# SCH_fluffly_2_2024-03-27.net
KiCad netlist of a schematic drawn in EasyEDA
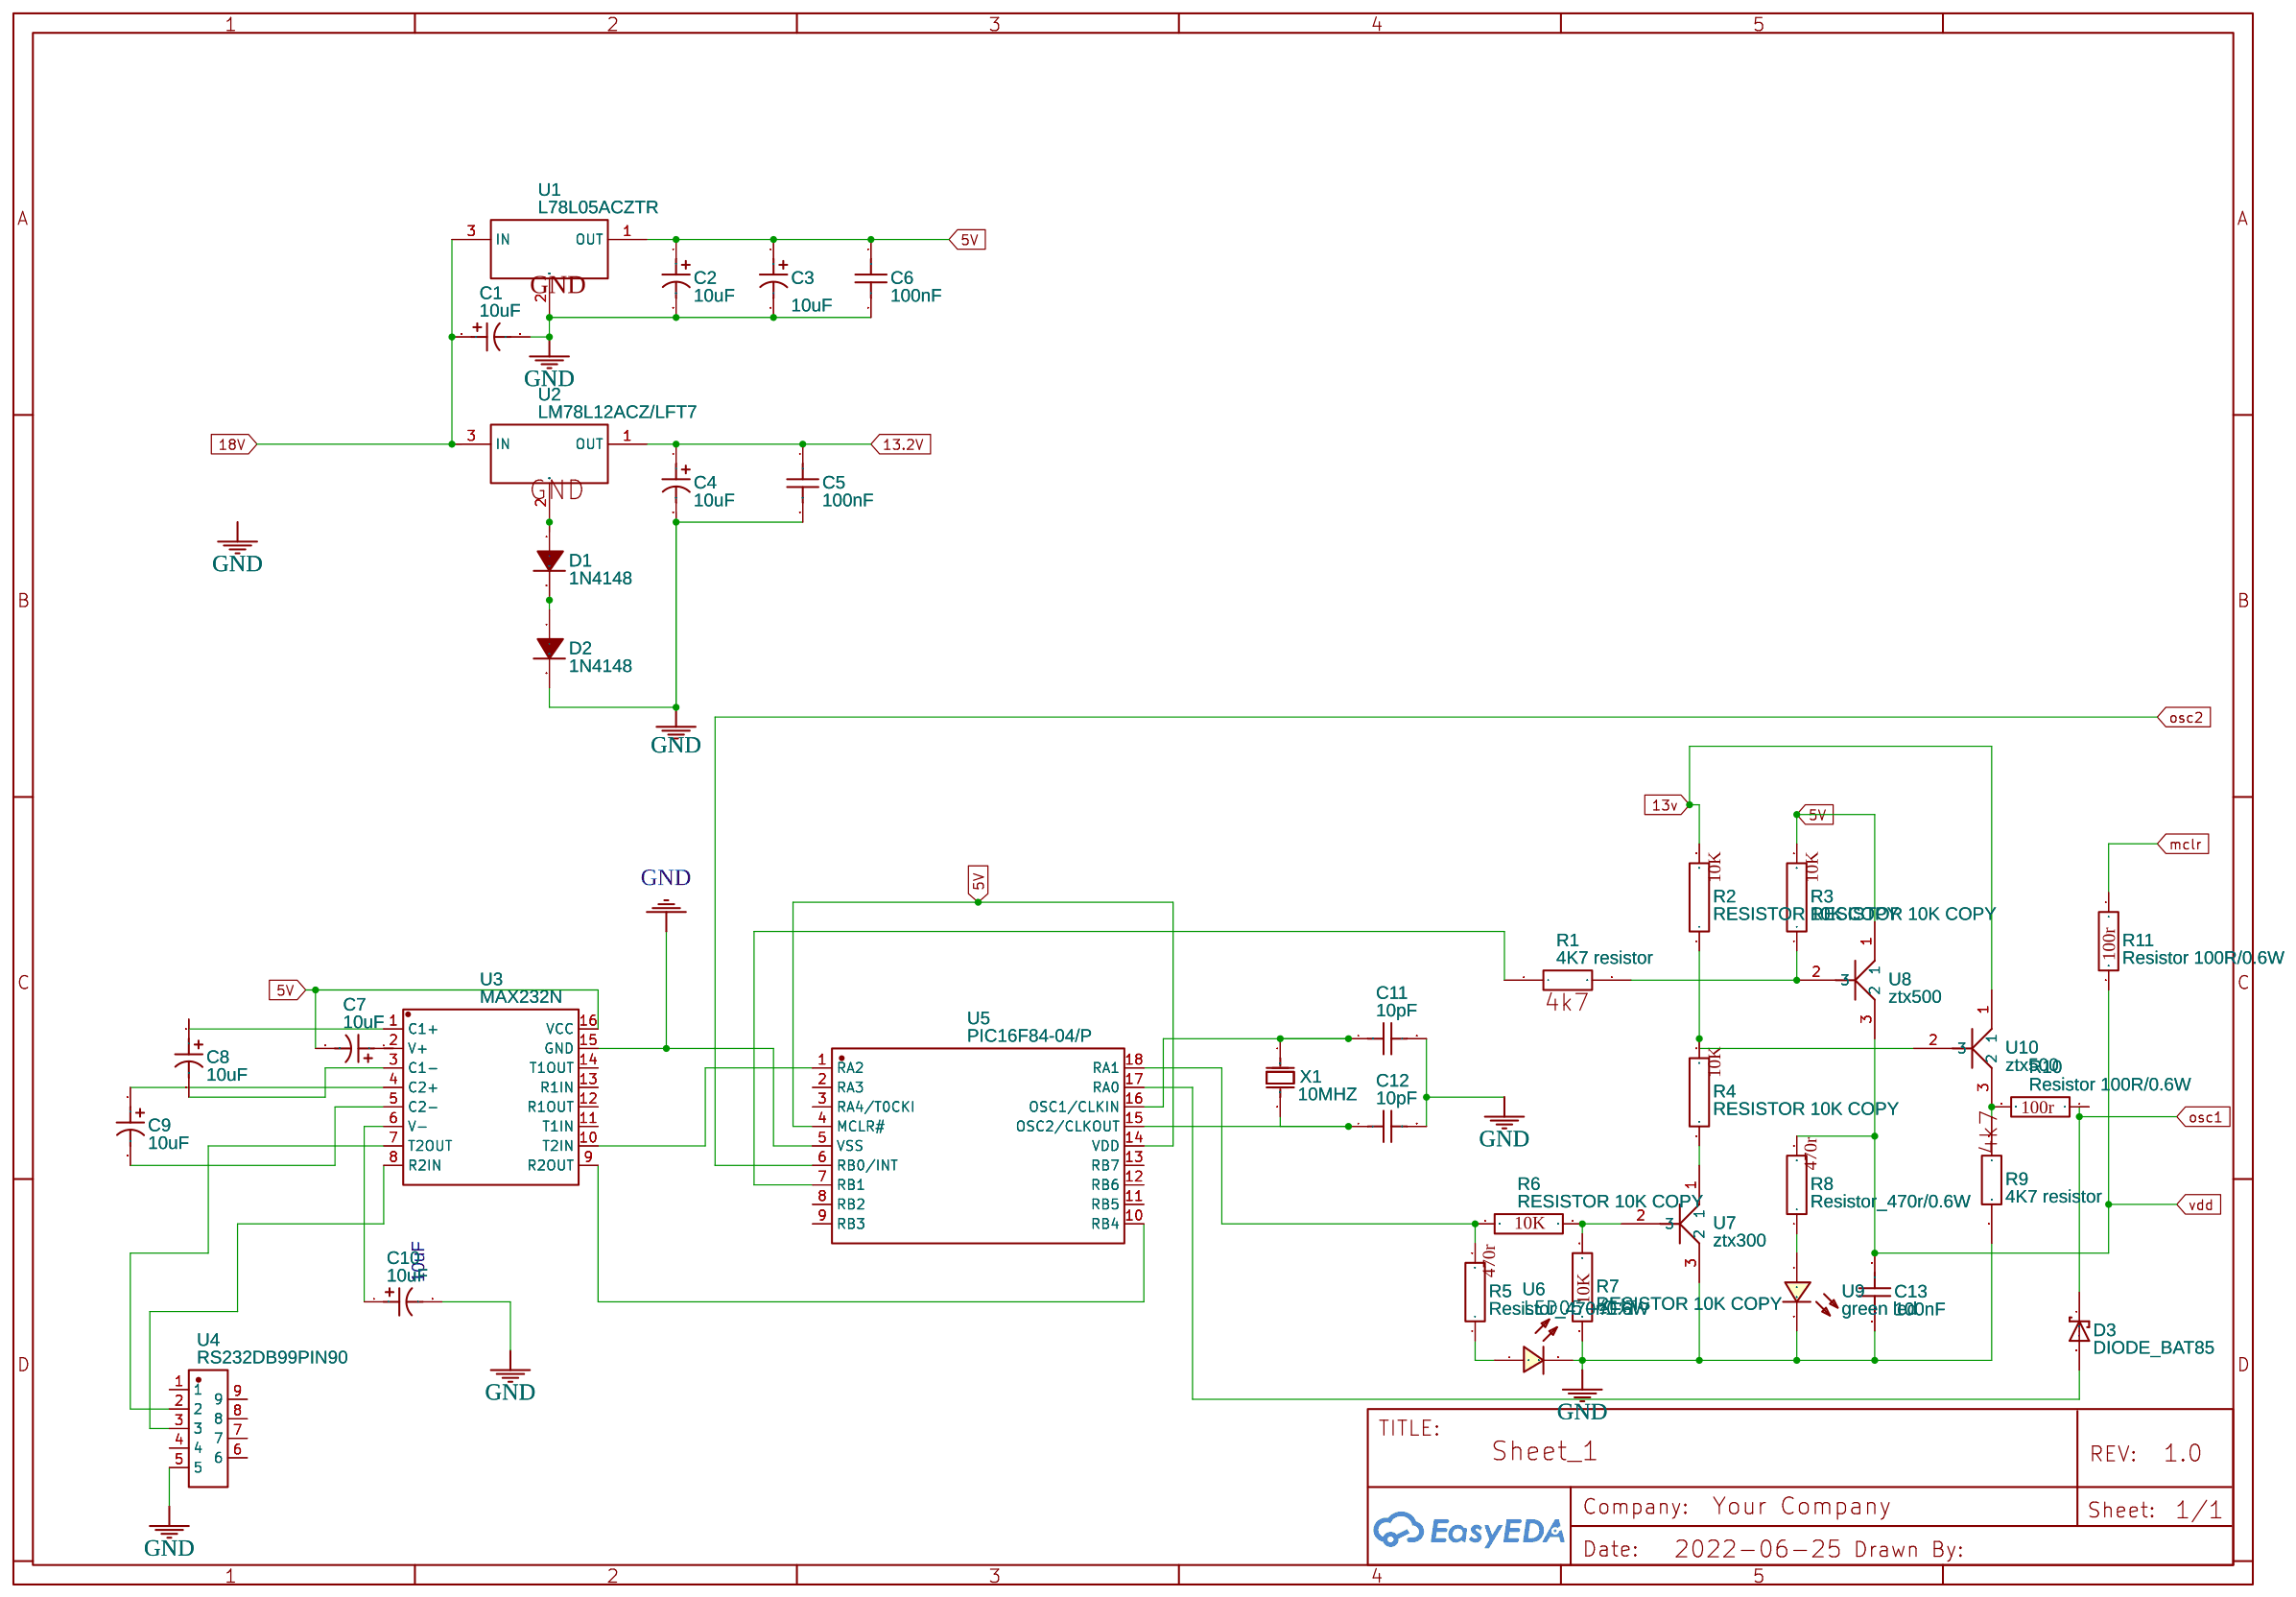
[diagram p0: schematic sheet]

(export (version "E")
  (design (tool "Eeschema 10.0.6"))
  (components
    (comp (ref "C1")
      (value "10uF")
      (fields (field (name "Manufacturer Part") "RFS-50V100MG3#") (field (name "Manufacturer") "ELNA(伊娜)"))
      (libsource (lib "") (part "RFS-50V100MG3#_3"))
    )
    (comp (ref "C2")
      (value "10uF")
      (fields (field (name "Manufacturer Part") "RFS-50V100MG3#") (field (name "Manufacturer") "ELNA(伊娜)"))
      (libsource (lib "") (part "RFS-50V100MG3#_1"))
    )
    (comp (ref "C3")
      (value "10uF")
      (fields (field (name "Manufacturer Part") "RFS-50V100MG3#") (field (name "Manufacturer") "ELNA(伊娜)"))
      (libsource (lib "") (part "RFS-50V100MG3#_1"))
    )
    (comp (ref "C4")
      (value "10uF")
      (fields (field (name "Manufacturer Part") "RFS-50V100MG3#") (field (name "Manufacturer") "ELNA(伊娜)"))
      (libsource (lib "") (part "RFS-50V100MG3#_1"))
    )
    (comp (ref "C5")
      (value "100nF")
      (fields
        (field (name "Manufacturer Part") "DCS104Z26Y5VF58L5A0")
        (field (name "Manufacturer") "SHM(南方宏明)")
      )
      (libsource (lib "") (part "DCS104Z26Y5VF58L5A0"))
    )
    (comp (ref "C6")
      (value "100nF")
      (fields
        (field (name "Manufacturer Part") "DCS104Z26Y5VF58L5A0")
        (field (name "Manufacturer") "SHM(南方宏明)")
      )
      (libsource (lib "") (part "DCS104Z26Y5VF58L5A0"))
    )
    (comp (ref "C7")
      (value "10uF")
      (fields (field (name "Manufacturer Part") "RFS-50V100MG3#") (field (name "Manufacturer") "ELNA(伊娜)"))
      (libsource (lib "") (part "RFS-50V100MG3#_2"))
    )
    (comp (ref "C8")
      (value "10uF")
      (fields (field (name "Manufacturer Part") "RFS-50V100MG3#") (field (name "Manufacturer") "ELNA(伊娜)"))
      (libsource (lib "") (part "RFS-50V100MG3#"))
    )
    (comp (ref "C9")
      (value "10uF")
      (fields (field (name "Manufacturer Part") "RFS-50V100MG3#") (field (name "Manufacturer") "ELNA(伊娜)"))
      (libsource (lib "") (part "RFS-50V100MG3#_1"))
    )
    (comp (ref "C10")
      (value "10uF")
      (fields (field (name "Manufacturer Part") "RFS-50V100MG3#") (field (name "Manufacturer") "ELNA(伊娜)"))
      (libsource (lib "") (part "RFS-50V100MG3#_4"))
    )
    (comp (ref "C11")
      (value "10pF")
      (fields (field (name "Manufacturer Part") "CC45SL3FD100JYNNA") (field (name "Manufacturer") "TDK"))
      (libsource (lib "") (part "CC45SL3FD100JYNNA"))
    )
    (comp (ref "C12")
      (value "10pF")
      (fields (field (name "Manufacturer Part") "CC45SL3FD100JYNNA") (field (name "Manufacturer") "TDK"))
      (libsource (lib "") (part "CC45SL3FD100JYNNA"))
    )
    (comp (ref "C13")
      (value "100nF")
      (fields
        (field (name "Manufacturer Part") "DCS104Z26Y5VF58L5A0")
        (field (name "Manufacturer") "SHM(南方宏明)")
      )
      (libsource (lib "") (part "DCS104Z26Y5VF58L5A0"))
    )
    (comp (ref "D1")
      (value "1N4148")
      (fields (field (name "Manufacturer") "SEMTECH"))
      (libsource (lib "") (part "1N4148"))
    )
    (comp (ref "D2")
      (value "1N4148")
      (fields (field (name "Manufacturer") "SEMTECH"))
      (libsource (lib "") (part "1N4148"))
    )
    (comp (ref "D3") (value "DIODE_BAT85") (libsource (lib "") (part "DIODE_BAT85")))
    (comp (ref "R1") (value "4K7 resistor") (libsource (lib "") (part "4K7 resistor")))
    (comp (ref "R2") (value "RESISTOR 10K COPY") (libsource (lib "") (part "RESISTOR 10K COPY")))
    (comp (ref "R3") (value "RESISTOR 10K COPY") (libsource (lib "") (part "RESISTOR 10K COPY")))
    (comp (ref "R4") (value "RESISTOR 10K COPY") (libsource (lib "") (part "RESISTOR 10K COPY")))
    (comp (ref "R5") (value "Resistor_470r/0.6W") (libsource (lib "") (part "Resistor_470r/0.6W")))
    (comp (ref "R6") (value "RESISTOR 10K COPY") (libsource (lib "") (part "RESISTOR 10K COPY_1")))
    (comp (ref "R7") (value "RESISTOR 10K COPY") (libsource (lib "") (part "RESISTOR 10K COPY_2")))
    (comp (ref "R8") (value "Resistor_470r/0.6W") (libsource (lib "") (part "Resistor_470r/0.6W")))
    (comp (ref "R9") (value "4K7 resistor") (libsource (lib "") (part "4K7 resistor_1")))
    (comp (ref "R10") (value "Resistor 100R/0.6W") (libsource (lib "") (part "Resistor 100R/0.6W_1")))
    (comp (ref "R11") (value "Resistor 100R/0.6W") (libsource (lib "") (part "Resistor 100R/0.6W")))
    (comp (ref "U1")
      (value "L78L05ACZTR")
      (fields (field (name "Manufacturer") "STMicroelectronics"))
      (libsource (lib "") (part "L78L05ACZTR"))
    )
    (comp (ref "U2")
      (value "LM78L12ACZ/LFT7")
      (fields (field (name "Manufacturer") "TI(德州仪器)"))
      (libsource (lib "") (part "LM78L12ACZ/LFT7"))
    )
    (comp (ref "U3")
      (value "MAX232N")
      (fields (field (name "Manufacturer") "Texas Instruments"))
      (libsource (lib "") (part "MAX232N"))
    )
    (comp (ref "U4")
      (value "RS232DB99PIN90")
      (fields (field (name "Manufacturer Part") "RS232DB99pin90度母座"))
      (libsource (lib "") (part "RS232DB99PIN90"))
    )
    (comp (ref "U5")
      (value "PIC16F84-04/P")
      (fields (field (name "Manufacturer") "Microchip Tech"))
      (libsource (lib "") (part "PIC16F84-04/P"))
    )
    (comp (ref "U6") (value "LED05-红灯") (libsource (lib "") (part "LED05-红灯")))
    (comp (ref "U7") (value "ztx300") (libsource (lib "") (part "transistor")))
    (comp (ref "U8") (value "ztx500") (libsource (lib "") (part "transistor")))
    (comp (ref "U9")
      (value "green led")
      (fields (field (name "Manufacturer Part") "LED05-红灯"))
      (libsource (lib "") (part "LED05-红灯_1"))
    )
    (comp (ref "U10") (value "ztx500") (libsource (lib "") (part "transistor")))
    (comp (ref "X1")
      (value "10MHZ")
      (fields (field (name "Manufacturer Part") "509-0400A2020-00") (field (name "Manufacturer") "XTY"))
      (libsource (lib "") (part "509-0400A2020-00"))
    )
  )
  (nets
    (net (code "1") (name "5V") (class "Default")
      (node (ref "C2") (pin "1") (pinfunction "1_1") (pintype "input"))
      (node (ref "C3") (pin "1") (pinfunction "1_1") (pintype "input"))
      (node (ref "C6") (pin "1") (pinfunction "1_1") (pintype "unspecified"))
      (node (ref "C7") (pin "2") (pinfunction "2_2") (pintype "input"))
      (node (ref "R3") (pin "2") (pinfunction "2_2") (pintype "unspecified"))
      (node (ref "U1") (pin "1") (pinfunction "OUT_1") (pintype "passive"))
      (node (ref "U3") (pin "16") (pinfunction "VCC_16") (pintype "unspecified"))
      (node (ref "U5") (pin "14") (pinfunction "VDD_14") (pintype "unspecified"))
      (node (ref "U5") (pin "4") (pinfunction "MCLR#_4") (pintype "unspecified"))
      (node (ref "U8") (pin "1") (pinfunction "1_1") (pintype "unspecified"))
    )
    (net (code "2") (name "13.2V") (class "Default")
      (node (ref "C4") (pin "1") (pinfunction "1_1") (pintype "input"))
      (node (ref "C5") (pin "1") (pinfunction "1_1") (pintype "unspecified"))
      (node (ref "U2") (pin "1") (pinfunction "OUT_1") (pintype "passive"))
    )
    (net (code "3") (name "13v") (class "Default")
      (node (ref "R2") (pin "2") (pinfunction "2_2") (pintype "unspecified"))
      (node (ref "U10") (pin "1") (pinfunction "1_1") (pintype "unspecified"))
    )
    (net (code "4") (name "18V") (class "Default")
      (node (ref "C1") (pin "1") (pinfunction "1_1") (pintype "input"))
      (node (ref "U1") (pin "3") (pinfunction "IN_3") (pintype "passive"))
      (node (ref "U2") (pin "3") (pinfunction "IN_3") (pintype "passive"))
    )
    (net (code "5") (name "GND") (class "Default")
      (node (ref "C1") (pin "2") (pinfunction "2_2") (pintype "input"))
      (node (ref "C10") (pin "2") (pinfunction "2_2") (pintype "input"))
      (node (ref "C11") (pin "2") (pinfunction "2_2") (pintype "unspecified"))
      (node (ref "C12") (pin "2") (pinfunction "2_2") (pintype "unspecified"))
      (node (ref "C13") (pin "2") (pinfunction "2_2") (pintype "unspecified"))
      (node (ref "C2") (pin "2") (pinfunction "2_2") (pintype "input"))
      (node (ref "C3") (pin "2") (pinfunction "2_2") (pintype "input"))
      (node (ref "C4") (pin "2") (pinfunction "2_2") (pintype "input"))
      (node (ref "C5") (pin "2") (pinfunction "2_2") (pintype "unspecified"))
      (node (ref "C6") (pin "2") (pinfunction "2_2") (pintype "unspecified"))
      (node (ref "D2") (pin "2") (pinfunction "C_2") (pintype "unspecified"))
      (node (ref "R7") (pin "1") (pinfunction "1_1") (pintype "unspecified"))
      (node (ref "R9") (pin "2") (pinfunction "2_2") (pintype "unspecified"))
      (node (ref "U1") (pin "2") (pinfunction "GND_2") (pintype "passive"))
      (node (ref "U3") (pin "15") (pinfunction "GND_15") (pintype "unspecified"))
      (node (ref "U4") (pin "5") (pinfunction "5_5") (pintype "unspecified"))
      (node (ref "U5") (pin "5") (pinfunction "VSS_5") (pintype "unspecified"))
      (node (ref "U6") (pin "2") (pinfunction "2_2") (pintype "unspecified"))
      (node (ref "U7") (pin "3") (pinfunction "2_3") (pintype "unspecified"))
      (node (ref "U9") (pin "2") (pinfunction "2_2") (pintype "unspecified"))
    )
    (net (code "6") (name "Net-(D1-A)") (class "Default")
      (node (ref "D1") (pin "1") (pinfunction "A_1") (pintype "unspecified"))
      (node (ref "U2") (pin "2") (pinfunction "GND_2") (pintype "passive"))
    )
    (net (code "7") (name "Net-(D1-C)") (class "Default")
      (node (ref "D1") (pin "2") (pinfunction "C_2") (pintype "unspecified"))
      (node (ref "D2") (pin "1") (pinfunction "A_1") (pintype "unspecified"))
    )
    (net (code "8") (name "Net-(D3-A)") (class "Default")
      (node (ref "D3") (pin "2") (pinfunction "A_2") (pintype "unspecified"))
      (node (ref "U5") (pin "17") (pinfunction "RA0_17") (pintype "unspecified"))
    )
    (net (code "9") (name "Net-(R4-Pad1)") (class "Default")
      (node (ref "R4") (pin "1") (pinfunction "1_1") (pintype "unspecified"))
      (node (ref "U7") (pin "1") (pinfunction "1_1") (pintype "unspecified"))
    )
    (net (code "10") (name "Net-(R5-Pad1)") (class "Default")
      (node (ref "R5") (pin "1") (pinfunction "1_1") (pintype "unspecified"))
      (node (ref "U6") (pin "1") (pinfunction "1_1") (pintype "unspecified"))
    )
    (net (code "11") (name "Net-(R8-Pad1)") (class "Default")
      (node (ref "R8") (pin "1") (pinfunction "1_1") (pintype "unspecified"))
      (node (ref "U9") (pin "1") (pinfunction "1_1") (pintype "unspecified"))
    )
    (net (code "12") (name "Net-(U3-C1+)") (class "Default")
      (node (ref "C8") (pin "1") (pinfunction "1_1") (pintype "input"))
      (node (ref "U3") (pin "1") (pinfunction "C1+_1") (pintype "unspecified"))
    )
    (net (code "13") (name "Net-(U3-C1-)") (class "Default")
      (node (ref "C8") (pin "2") (pinfunction "2_2") (pintype "input"))
      (node (ref "U3") (pin "3") (pinfunction "C1-_3") (pintype "unspecified"))
    )
    (net (code "14") (name "Net-(U3-C2+)") (class "Default")
      (node (ref "C9") (pin "1") (pinfunction "1_1") (pintype "input"))
      (node (ref "U3") (pin "4") (pinfunction "C2+_4") (pintype "unspecified"))
    )
    (net (code "15") (name "Net-(U3-C2-)") (class "Default")
      (node (ref "C9") (pin "2") (pinfunction "2_2") (pintype "input"))
      (node (ref "U3") (pin "5") (pinfunction "C2-_5") (pintype "unspecified"))
    )
    (net (code "16") (name "Net-(U3-R2IN)") (class "Default")
      (node (ref "U3") (pin "8") (pinfunction "R2IN_8") (pintype "unspecified"))
      (node (ref "U4") (pin "3") (pinfunction "3_3") (pintype "unspecified"))
    )
    (net (code "17") (name "Net-(U3-R2OUT)") (class "Default")
      (node (ref "U3") (pin "9") (pinfunction "R2OUT_9") (pintype "unspecified"))
      (node (ref "U5") (pin "10") (pinfunction "RB4_10") (pintype "unspecified"))
    )
    (net (code "18") (name "Net-(U3-T2IN)") (class "Default")
      (node (ref "U3") (pin "10") (pinfunction "T2IN_10") (pintype "unspecified"))
      (node (ref "U5") (pin "1") (pinfunction "RA2_1") (pintype "unspecified"))
    )
    (net (code "19") (name "Net-(U3-T2OUT)") (class "Default")
      (node (ref "U3") (pin "7") (pinfunction "T2OUT_7") (pintype "unspecified"))
      (node (ref "U4") (pin "2") (pinfunction "2_2") (pintype "unspecified"))
    )
    (net (code "20") (name "Net-(U3-V+)") (class "Default")
      (node (ref "C7") (pin "1") (pinfunction "1_1") (pintype "input"))
      (node (ref "U3") (pin "2") (pinfunction "V+_2") (pintype "unspecified"))
    )
    (net (code "21") (name "Net-(U3-V-)") (class "Default")
      (node (ref "C10") (pin "1") (pinfunction "1_1") (pintype "input"))
      (node (ref "U3") (pin "6") (pinfunction "V-_6") (pintype "unspecified"))
    )
    (net (code "22") (name "Net-(U5-OSC1{slash}CLKIN)") (class "Default")
      (node (ref "C11") (pin "1") (pinfunction "1_1") (pintype "unspecified"))
      (node (ref "U5") (pin "16") (pinfunction "OSC1/CLKIN_16") (pintype "unspecified"))
      (node (ref "X1") (pin "1") (pinfunction "OSC1_1") (pintype "input"))
    )
    (net (code "23") (name "Net-(U5-OSC2{slash}CLKOUT)") (class "Default")
      (node (ref "C12") (pin "1") (pinfunction "1_1") (pintype "unspecified"))
      (node (ref "U5") (pin "15") (pinfunction "OSC2/CLKOUT_15") (pintype "unspecified"))
      (node (ref "X1") (pin "2") (pinfunction "OSC2_2") (pintype "input"))
    )
    (net (code "24") (name "Net-(U5-RA1)") (class "Default")
      (node (ref "R5") (pin "2") (pinfunction "2_2") (pintype "unspecified"))
      (node (ref "R6") (pin "2") (pinfunction "2_2") (pintype "unspecified"))
      (node (ref "U5") (pin "18") (pinfunction "RA1_18") (pintype "unspecified"))
    )
    (net (code "25") (name "Net-(U5-RB1)") (class "Default")
      (node (ref "R1") (pin "1") (pinfunction "1_1") (pintype "unspecified"))
      (node (ref "U5") (pin "7") (pinfunction "RB1_7") (pintype "unspecified"))
    )
    (net (code "26") (name "Net-(U7-3)") (class "Default")
      (node (ref "R6") (pin "1") (pinfunction "1_1") (pintype "unspecified"))
      (node (ref "R7") (pin "2") (pinfunction "2_2") (pintype "unspecified"))
      (node (ref "U7") (pin "2") (pinfunction "3_2") (pintype "unspecified"))
    )
    (net (code "27") (name "Net-(U8-3)") (class "Default")
      (node (ref "R1") (pin "2") (pinfunction "2_2") (pintype "unspecified"))
      (node (ref "R3") (pin "1") (pinfunction "1_1") (pintype "unspecified"))
      (node (ref "U8") (pin "2") (pinfunction "3_2") (pintype "unspecified"))
    )
    (net (code "28") (name "Net-(U10-2)") (class "Default")
      (node (ref "R10") (pin "2") (pinfunction "2_2") (pintype "unspecified"))
      (node (ref "R9") (pin "1") (pinfunction "1_1") (pintype "unspecified"))
      (node (ref "U10") (pin "3") (pinfunction "2_3") (pintype "unspecified"))
    )
    (net (code "29") (name "Net-(U10-3)") (class "Default")
      (node (ref "R2") (pin "1") (pinfunction "1_1") (pintype "unspecified"))
      (node (ref "R4") (pin "2") (pinfunction "2_2") (pintype "unspecified"))
      (node (ref "U10") (pin "2") (pinfunction "3_2") (pintype "unspecified"))
    )
    (net (code "30") (name "mclr") (class "Default")
      (node (ref "R11") (pin "1") (pinfunction "1_1") (pintype "unspecified"))
    )
    (net (code "31") (name "osc1") (class "Default")
      (node (ref "D3") (pin "1") (pinfunction "K_1") (pintype "unspecified"))
      (node (ref "R10") (pin "1") (pinfunction "1_1") (pintype "unspecified"))
    )
    (net (code "32") (name "osc2") (class "Default")
      (node (ref "U5") (pin "6") (pinfunction "RB0/INT_6") (pintype "unspecified"))
    )
    (net (code "33") (name "unconnected-(U3-R1IN-Pad13)") (class "Default")
      (node (ref "U3") (pin "13") (pinfunction "R1IN_13") (pintype "unspecified"))
    )
    (net (code "34") (name "unconnected-(U3-R1OUT-Pad12)") (class "Default")
      (node (ref "U3") (pin "12") (pinfunction "R1OUT_12") (pintype "unspecified"))
    )
    (net (code "35") (name "unconnected-(U3-T1IN-Pad11)") (class "Default")
      (node (ref "U3") (pin "11") (pinfunction "T1IN_11") (pintype "unspecified"))
    )
    (net (code "36") (name "unconnected-(U3-T1OUT-Pad14)") (class "Default")
      (node (ref "U3") (pin "14") (pinfunction "T1OUT_14") (pintype "unspecified"))
    )
    (net (code "37") (name "unconnected-(U4-Pad1)") (class "Default")
      (node (ref "U4") (pin "1") (pinfunction "1_1") (pintype "unspecified"))
    )
    (net (code "38") (name "unconnected-(U4-Pad4)") (class "Default")
      (node (ref "U4") (pin "4") (pinfunction "4_4") (pintype "unspecified"))
    )
    (net (code "39") (name "unconnected-(U4-Pad6)") (class "Default")
      (node (ref "U4") (pin "6") (pinfunction "6_6") (pintype "unspecified"))
    )
    (net (code "40") (name "unconnected-(U4-Pad7)") (class "Default")
      (node (ref "U4") (pin "7") (pinfunction "7_7") (pintype "unspecified"))
    )
    (net (code "41") (name "unconnected-(U4-Pad8)") (class "Default")
      (node (ref "U4") (pin "8") (pinfunction "8_8") (pintype "unspecified"))
    )
    (net (code "42") (name "unconnected-(U4-Pad9)") (class "Default")
      (node (ref "U4") (pin "9") (pinfunction "9_9") (pintype "unspecified"))
    )
    (net (code "43") (name "unconnected-(U5-RA3-Pad2)") (class "Default")
      (node (ref "U5") (pin "2") (pinfunction "RA3_2") (pintype "unspecified"))
    )
    (net (code "44") (name "unconnected-(U5-RA4{slash}T0CKI-Pad3)") (class "Default")
      (node (ref "U5") (pin "3") (pinfunction "RA4/T0CKI_3") (pintype "unspecified"))
    )
    (net (code "45") (name "unconnected-(U5-RB2-Pad8)") (class "Default")
      (node (ref "U5") (pin "8") (pinfunction "RB2_8") (pintype "unspecified"))
    )
    (net (code "46") (name "unconnected-(U5-RB3-Pad9)") (class "Default")
      (node (ref "U5") (pin "9") (pinfunction "RB3_9") (pintype "unspecified"))
    )
    (net (code "47") (name "unconnected-(U5-RB5-Pad11)") (class "Default")
      (node (ref "U5") (pin "11") (pinfunction "RB5_11") (pintype "unspecified"))
    )
    (net (code "48") (name "unconnected-(U5-RB6-Pad12)") (class "Default")
      (node (ref "U5") (pin "12") (pinfunction "RB6_12") (pintype "unspecified"))
    )
    (net (code "49") (name "unconnected-(U5-RB7-Pad13)") (class "Default")
      (node (ref "U5") (pin "13") (pinfunction "RB7_13") (pintype "unspecified"))
    )
    (net (code "50") (name "vdd") (class "Default")
      (node (ref "C13") (pin "1") (pinfunction "1_1") (pintype "unspecified"))
      (node (ref "R11") (pin "2") (pinfunction "2_2") (pintype "unspecified"))
      (node (ref "R8") (pin "2") (pinfunction "2_2") (pintype "unspecified"))
      (node (ref "U8") (pin "3") (pinfunction "2_3") (pintype "unspecified"))
    )
  )
)
